# Elekid_04.net
KiCad netlist of a schematic drawn in Altium Designer
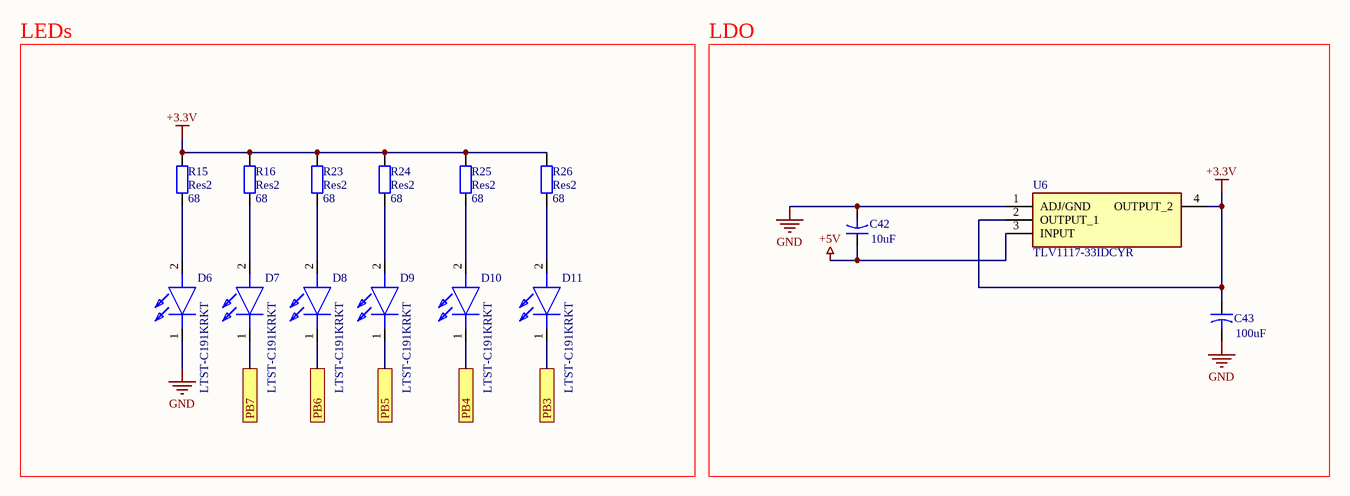
[diagram p0: Elekid_04.SchDoc]

(export (version "E")
  (design (tool "Eeschema 10.0.6"))
  (components
    (comp (ref "C42")
      (value "10uF")
      (footprint "C0805")
      (description "Capacitor")
      (fields (field (name "Comment") "Cap2") (field (name "PUBLISHER") "Altium Limited"))
      (libsource (lib "Miscellaneous Devices") (part "Cap2"))
    )
    (comp (ref "C43")
      (value "100uF")
      (footprint "C0805")
      (description "Capacitor")
      (fields (field (name "Comment") "Cap2") (field (name "PUBLISHER") "Altium Limited"))
      (libsource (lib "Miscellaneous Devices") (part "Cap2"))
    )
    (comp (ref "D6")
      (value "LTST-C191KRKT")
      (footprint "Embedded:LEDC1608X55N")
      (description "LED")
      (fields (field (name "MOUSER PART NUMBER") "859-LTST-C191KRKT"))
      (libsource (lib "*") (part "LTST-C191KRKT"))
    )
    (comp (ref "D7")
      (value "LTST-C191KRKT")
      (footprint "Embedded:LEDC1608X55N")
      (description "LED")
      (fields (field (name "MOUSER PART NUMBER") "859-LTST-C191KRKT"))
      (libsource (lib "*") (part "LTST-C191KRKT"))
    )
    (comp (ref "D8")
      (value "LTST-C191KRKT")
      (footprint "Embedded:LEDC1608X55N")
      (description "LED")
      (fields (field (name "MOUSER PART NUMBER") "859-LTST-C191KRKT"))
      (libsource (lib "*") (part "LTST-C191KRKT"))
    )
    (comp (ref "D9")
      (value "LTST-C191KRKT")
      (footprint "Embedded:LEDC1608X55N")
      (description "LED")
      (fields (field (name "MOUSER PART NUMBER") "859-LTST-C191KRKT"))
      (libsource (lib "*") (part "LTST-C191KRKT"))
    )
    (comp (ref "D10")
      (value "LTST-C191KRKT")
      (footprint "Embedded:LEDC1608X55N")
      (description "LED")
      (fields (field (name "MOUSER PART NUMBER") "859-LTST-C191KRKT"))
      (libsource (lib "*") (part "LTST-C191KRKT"))
    )
    (comp (ref "D11")
      (value "LTST-C191KRKT")
      (footprint "Embedded:LEDC1608X55N")
      (description "LED")
      (fields (field (name "MOUSER PART NUMBER") "859-LTST-C191KRKT"))
      (libsource (lib "*") (part "LTST-C191KRKT"))
    )
    (comp (ref "R15")
      (value "Res2")
      (footprint "C0805")
      (description "Resistor")
      (fields (field (name "ALTIUM_VALUE") "68") (field (name "PUBLISHER") "Altium Limited"))
      (libsource (lib "Miscellaneous Devices") (part "Res2"))
    )
    (comp (ref "R16")
      (value "Res2")
      (footprint "C0805")
      (description "Resistor")
      (fields (field (name "ALTIUM_VALUE") "68") (field (name "PUBLISHER") "Altium Limited"))
      (libsource (lib "Miscellaneous Devices") (part "Res2"))
    )
    (comp (ref "R23")
      (value "Res2")
      (footprint "C0805")
      (description "Resistor")
      (fields (field (name "ALTIUM_VALUE") "68") (field (name "PUBLISHER") "Altium Limited"))
      (libsource (lib "Miscellaneous Devices") (part "Res2"))
    )
    (comp (ref "R24")
      (value "Res2")
      (footprint "C0805")
      (description "Resistor")
      (fields (field (name "ALTIUM_VALUE") "68") (field (name "PUBLISHER") "Altium Limited"))
      (libsource (lib "Miscellaneous Devices") (part "Res2"))
    )
    (comp (ref "R25")
      (value "Res2")
      (footprint "C0805")
      (description "Resistor")
      (fields (field (name "ALTIUM_VALUE") "68") (field (name "PUBLISHER") "Altium Limited"))
      (libsource (lib "Miscellaneous Devices") (part "Res2"))
    )
    (comp (ref "R26")
      (value "Res2")
      (footprint "C0805")
      (description "Resistor")
      (fields (field (name "ALTIUM_VALUE") "68") (field (name "PUBLISHER") "Altium Limited"))
      (libsource (lib "Miscellaneous Devices") (part "Res2"))
    )
    (comp (ref "U6")
      (value "TLV1117-33IDCYR")
      (footprint "Embedded:SOT230P700X180-4N")
      (description "Integrated Circuit")
      (fields
        (field (name "MANUFACTURER_PART_NUMBER") "TLV1117-33CDCYR")
        (field (name "MOUSER PART NUMBER") "595-TLV1117-33CDCYR")
      )
      (libsource (lib "*") (part "TLV1117-33CDCYR"))
    )
  )
  (nets
    (net (code "1") (name "+3.3V") (class "Default")
      (node (ref "C43") (pin "1") (pinfunction "1_1") (pintype "passive"))
      (node (ref "R15") (pin "2") (pinfunction "2_2") (pintype "passive"))
      (node (ref "R16") (pin "2") (pinfunction "2_2") (pintype "passive"))
      (node (ref "R23") (pin "2") (pinfunction "2_2") (pintype "passive"))
      (node (ref "R24") (pin "2") (pinfunction "2_2") (pintype "passive"))
      (node (ref "R25") (pin "2") (pinfunction "2_2") (pintype "passive"))
      (node (ref "R26") (pin "2") (pinfunction "2_2") (pintype "passive"))
      (node (ref "U6") (pin "2") (pinfunction "OUTPUT_1_2") (pintype "passive"))
      (node (ref "U6") (pin "4") (pinfunction "OUTPUT_2_4") (pintype "passive"))
    )
    (net (code "2") (name "+5V") (class "Default")
      (node (ref "C42") (pin "1") (pinfunction "1_1") (pintype "passive"))
      (node (ref "U6") (pin "3") (pinfunction "INPUT_3") (pintype "passive"))
    )
    (net (code "3") (name "/PB3") (class "Default")
      (node (ref "D11") (pin "1") (pinfunction "K_1") (pintype "passive"))
    )
    (net (code "4") (name "/PB4") (class "Default")
      (node (ref "D10") (pin "1") (pinfunction "K_1") (pintype "passive"))
    )
    (net (code "5") (name "/PB5") (class "Default")
      (node (ref "D9") (pin "1") (pinfunction "K_1") (pintype "passive"))
    )
    (net (code "6") (name "/PB6") (class "Default")
      (node (ref "D8") (pin "1") (pinfunction "K_1") (pintype "passive"))
    )
    (net (code "7") (name "/PB7") (class "Default")
      (node (ref "D7") (pin "1") (pinfunction "K_1") (pintype "passive"))
    )
    (net (code "8") (name "GND") (class "Default")
      (node (ref "C42") (pin "2") (pinfunction "2_2") (pintype "passive"))
      (node (ref "C43") (pin "2") (pinfunction "2_2") (pintype "passive"))
      (node (ref "D6") (pin "1") (pinfunction "K_1") (pintype "passive"))
      (node (ref "U6") (pin "1") (pinfunction "ADJ/GND_1") (pintype "passive"))
    )
    (net (code "9") (name "Net-(D6-A)") (class "Default")
      (node (ref "D6") (pin "2") (pinfunction "A_2") (pintype "passive"))
      (node (ref "R15") (pin "1") (pinfunction "1_1") (pintype "passive"))
    )
    (net (code "10") (name "Net-(D7-A)") (class "Default")
      (node (ref "D7") (pin "2") (pinfunction "A_2") (pintype "passive"))
      (node (ref "R16") (pin "1") (pinfunction "1_1") (pintype "passive"))
    )
    (net (code "11") (name "Net-(D8-A)") (class "Default")
      (node (ref "D8") (pin "2") (pinfunction "A_2") (pintype "passive"))
      (node (ref "R23") (pin "1") (pinfunction "1_1") (pintype "passive"))
    )
    (net (code "12") (name "Net-(D9-A)") (class "Default")
      (node (ref "D9") (pin "2") (pinfunction "A_2") (pintype "passive"))
      (node (ref "R24") (pin "1") (pinfunction "1_1") (pintype "passive"))
    )
    (net (code "13") (name "Net-(D10-A)") (class "Default")
      (node (ref "D10") (pin "2") (pinfunction "A_2") (pintype "passive"))
      (node (ref "R25") (pin "1") (pinfunction "1_1") (pintype "passive"))
    )
    (net (code "14") (name "Net-(D11-A)") (class "Default")
      (node (ref "D11") (pin "2") (pinfunction "A_2") (pintype "passive"))
      (node (ref "R26") (pin "1") (pinfunction "1_1") (pintype "passive"))
    )
  )
)
